# SDR-RPI_Shield_3_0.net
KiCad netlist of a schematic drawn in EAGLE
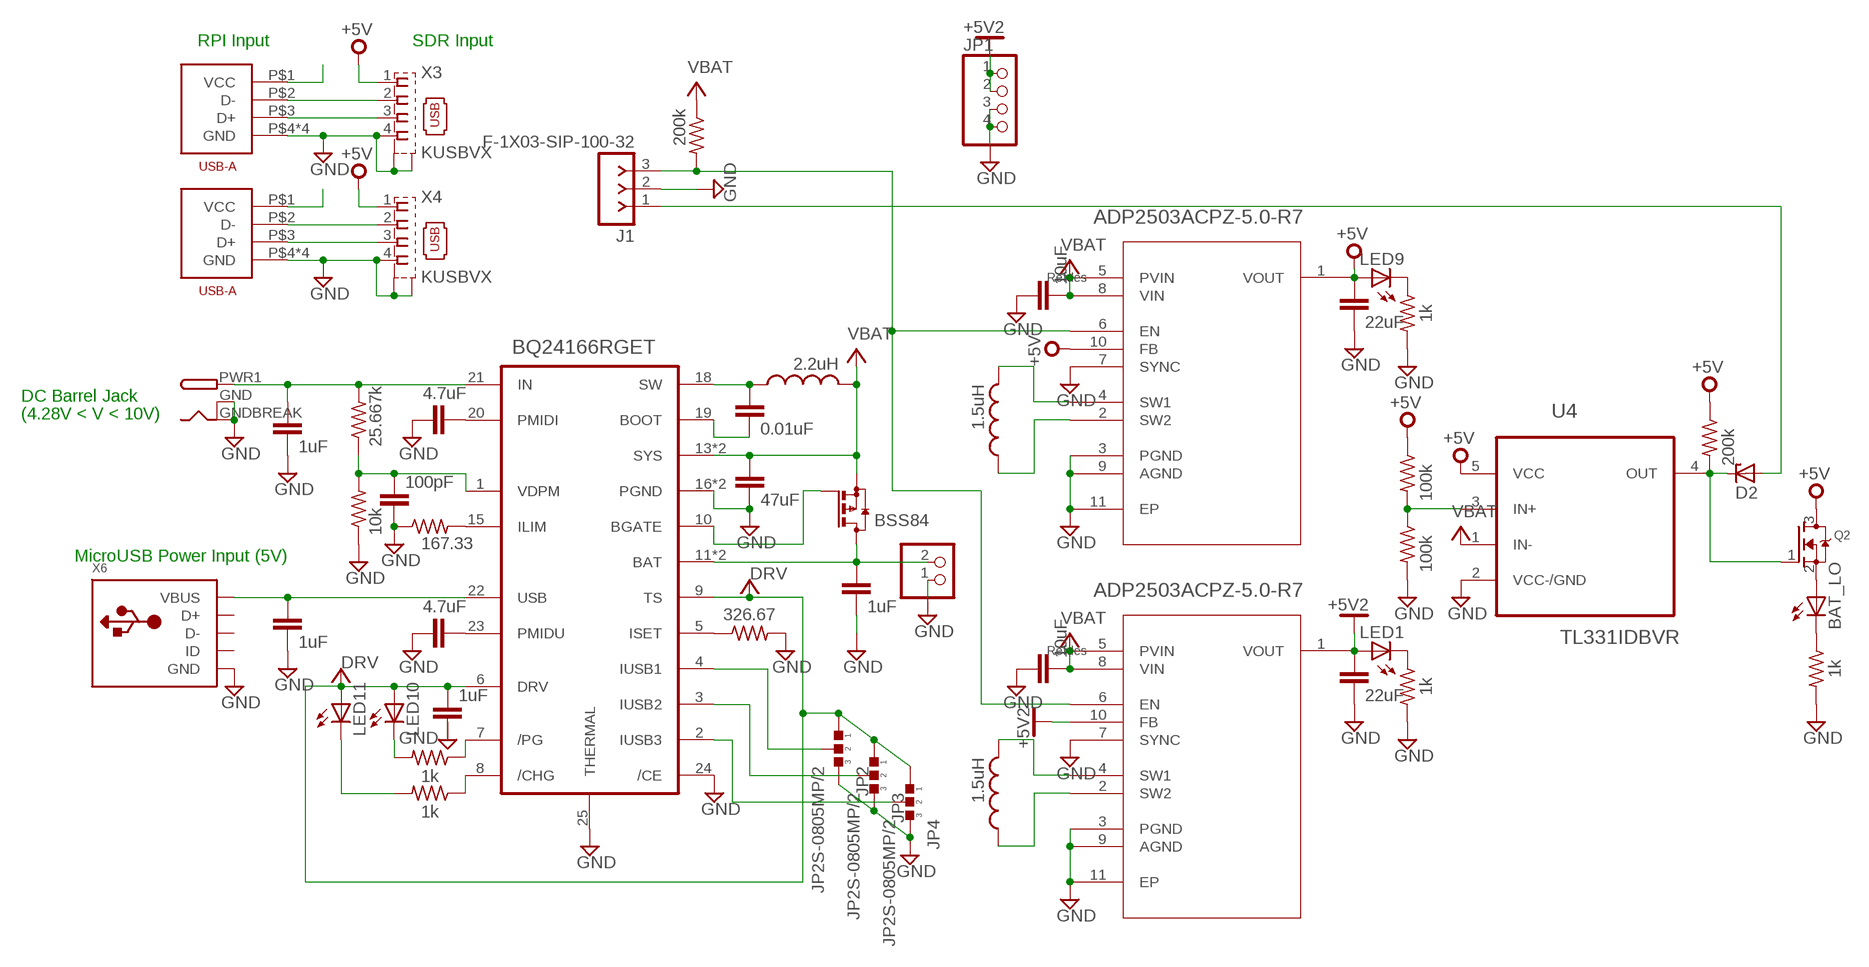
[diagram p0: schematic, sheet 1]

(export (version "E")
  (design (tool "Eeschema 10.0.6"))
  (components
    (comp (ref "BAT_LO")
      (value "LED_ESML0603")
      (footprint "eagle-import:LED_SML0603")
      (libsource (lib "eagle-import") (part "LED_ESML0603"))
    )
    (comp (ref "C1")
      (value "1uF")
      (footprint "eagle-import:C0805")
      (libsource (lib "eagle-import") (part "C-EUC0805"))
    )
    (comp (ref "C2")
      (value "4.7uF")
      (footprint "eagle-import:C0805")
      (libsource (lib "eagle-import") (part "C-EUC0805"))
    )
    (comp (ref "C3")
      (value "1uF")
      (footprint "eagle-import:C0805")
      (libsource (lib "eagle-import") (part "C-EUC0805"))
    )
    (comp (ref "C4")
      (value "4.7uF")
      (footprint "eagle-import:C0805")
      (libsource (lib "eagle-import") (part "C-EUC0805"))
    )
    (comp (ref "C5")
      (value "1uF")
      (footprint "eagle-import:C0805")
      (libsource (lib "eagle-import") (part "C-EUC0805"))
    )
    (comp (ref "C6")
      (value "0.01uF")
      (footprint "eagle-import:C0805")
      (libsource (lib "eagle-import") (part "C-EUC0805"))
    )
    (comp (ref "C7")
      (value "22uF")
      (footprint "eagle-import:C0805")
      (libsource (lib "eagle-import") (part "C-EUC0805"))
    )
    (comp (ref "C8")
      (value "1uF")
      (footprint "eagle-import:C0805")
      (libsource (lib "eagle-import") (part "C-EUC0805"))
    )
    (comp (ref "C9")
      (value "47uF")
      (footprint "eagle-import:C0805")
      (libsource (lib "eagle-import") (part "C-EUC0805"))
    )
    (comp (ref "C10")
      (value "10uF")
      (footprint "eagle-import:C0805")
      (libsource (lib "eagle-import") (part "C-EUC0805"))
    )
    (comp (ref "C11")
      (value "10uF")
      (footprint "eagle-import:C0805")
      (libsource (lib "eagle-import") (part "C-EUC0805"))
    )
    (comp (ref "C12")
      (value "22uF")
      (footprint "eagle-import:C0805")
      (libsource (lib "eagle-import") (part "C-EUC0805"))
    )
    (comp (ref "C17")
      (value "100pF")
      (footprint "eagle-import:C0805")
      (libsource (lib "eagle-import") (part "C-EUC0805"))
    )
    (comp (ref "CN1")
      (value "JST_2PIN-SMT")
      (footprint "eagle-import:JST-PH-2-SMT")
      (libsource (lib "eagle-import") (part "JST_2PIN-SMT"))
    )
    (comp (ref "CN3")
      (value "DCBARRELSMT")
      (footprint "eagle-import:DCJACK_2MM_SMT")
      (libsource (lib "eagle-import") (part "DCBARRELSMT"))
    )
    (comp (ref "D2")
      (value "ZENER-DIODESOD80C")
      (footprint "eagle-import:SOD80C")
      (libsource (lib "eagle-import") (part "ZENER-DIODESOD80C"))
    )
    (comp (ref "J1")
      (value "F-1X03-SIP-100-32")
      (footprint "eagle-import:SIP-100-03-32")
      (libsource (lib "eagle-import") (part "F-1X03-SIP-100-32"))
    )
    (comp (ref "JP1")
      (value "PINHD-1X4")
      (footprint "eagle-import:1X04")
      (libsource (lib "eagle-import") (part "PINHD-1X4"))
    )
    (comp (ref "JP2")
      (value "JP2S-0805MP/2")
      (footprint "eagle-import:R0805MP_2")
      (libsource (lib "eagle-import") (part "JP2S-0805MP/2"))
    )
    (comp (ref "JP3")
      (value "JP2S-0805MP/2")
      (footprint "eagle-import:R0805MP_2")
      (libsource (lib "eagle-import") (part "JP2S-0805MP/2"))
    )
    (comp (ref "JP4")
      (value "JP2S-0805MP/2")
      (footprint "eagle-import:R0805MP_2")
      (libsource (lib "eagle-import") (part "JP2S-0805MP/2"))
    )
    (comp (ref "L1")
      (value "2.2uH")
      (footprint "eagle-import:L1812")
      (libsource (lib "eagle-import") (part "L-USL1812"))
    )
    (comp (ref "L2")
      (value "1.5uH")
      (footprint "eagle-import:L1812")
      (libsource (lib "eagle-import") (part "L-USL1812"))
    )
    (comp (ref "L3")
      (value "1.5uH")
      (footprint "eagle-import:L1812")
      (libsource (lib "eagle-import") (part "L-USL1812"))
    )
    (comp (ref "LED1")
      (value "LED_ESML0603")
      (footprint "eagle-import:LED_SML0603")
      (libsource (lib "eagle-import") (part "LED_ESML0603"))
    )
    (comp (ref "LED9")
      (value "LED_ESML0603")
      (footprint "eagle-import:LED_SML0603")
      (libsource (lib "eagle-import") (part "LED_ESML0603"))
    )
    (comp (ref "LED10")
      (value "LED_ESML0603")
      (footprint "eagle-import:LED_SML0603")
      (libsource (lib "eagle-import") (part "LED_ESML0603"))
    )
    (comp (ref "LED11")
      (value "LED_ESML0603")
      (footprint "eagle-import:LED_SML0603")
      (libsource (lib "eagle-import") (part "LED_ESML0603"))
    )
    (comp (ref "Q1")
      (value "BSS84")
      (footprint "eagle-import:SOT23")
      (libsource (lib "eagle-import") (part "BSS84"))
    )
    (comp (ref "Q2")
      (value "MOSFET-NREFLOW")
      (footprint "eagle-import:SOT23")
      (libsource (lib "eagle-import") (part "MOSFET-NREFLOW"))
    )
    (comp (ref "R1")
      (value "25.667k")
      (footprint "eagle-import:M0805")
      (libsource (lib "eagle-import") (part "R-US_M0805"))
    )
    (comp (ref "R2")
      (value "10k")
      (footprint "eagle-import:M0805")
      (libsource (lib "eagle-import") (part "R-US_M0805"))
    )
    (comp (ref "R3")
      (value "167.33")
      (footprint "eagle-import:M0805")
      (libsource (lib "eagle-import") (part "R-US_M0805"))
    )
    (comp (ref "R4")
      (value "1k")
      (footprint "eagle-import:M0805")
      (libsource (lib "eagle-import") (part "R-US_M0805"))
    )
    (comp (ref "R5")
      (value "1k")
      (footprint "eagle-import:M0805")
      (libsource (lib "eagle-import") (part "R-US_M0805"))
    )
    (comp (ref "R6")
      (value "326.67")
      (footprint "eagle-import:M0805")
      (libsource (lib "eagle-import") (part "R-US_M0805"))
    )
    (comp (ref "R7")
      (value "1k")
      (footprint "eagle-import:M0805")
      (libsource (lib "eagle-import") (part "R-US_M0805"))
    )
    (comp (ref "R8")
      (value "1k")
      (footprint "eagle-import:M0805")
      (libsource (lib "eagle-import") (part "R-US_M0805"))
    )
    (comp (ref "R9")
      (value "100k")
      (footprint "eagle-import:M0805")
      (libsource (lib "eagle-import") (part "R-US_M0805"))
    )
    (comp (ref "R10")
      (value "100k")
      (footprint "eagle-import:M0805")
      (libsource (lib "eagle-import") (part "R-US_M0805"))
    )
    (comp (ref "R11")
      (value "200k")
      (footprint "eagle-import:M0805")
      (libsource (lib "eagle-import") (part "R-US_M0805"))
    )
    (comp (ref "R12")
      (value "1k")
      (footprint "eagle-import:M0805")
      (libsource (lib "eagle-import") (part "R-US_M0805"))
    )
    (comp (ref "R16")
      (value "200k")
      (footprint "eagle-import:M0805")
      (libsource (lib "eagle-import") (part "R-US_M0805"))
    )
    (comp (ref "U$1")
      (value "USB-A")
      (footprint "eagle-import:USB-A")
      (libsource (lib "eagle-import") (part "USB-A"))
    )
    (comp (ref "U$2")
      (value "USB-A")
      (footprint "eagle-import:USB-A")
      (libsource (lib "eagle-import") (part "USB-A"))
    )
    (comp (ref "U1")
      (value "BQ24166RGET")
      (footprint "eagle-import:QFN50P400X400X100-25N")
      (libsource (lib "eagle-import") (part "BQ24166RGET"))
    )
    (comp (ref "U2")
      (value "ADP2503ACPZ-5.0-R7")
      (footprint "eagle-import:DFN300X300X80-11N")
      (libsource (lib "eagle-import") (part "ADP2503ACPZ-5.0-R7"))
    )
    (comp (ref "U3")
      (value "ADP2503ACPZ-5.0-R7")
      (footprint "eagle-import:DFN300X300X80-11N")
      (libsource (lib "eagle-import") (part "ADP2503ACPZ-5.0-R7"))
    )
    (comp (ref "U4")
      (value "TL331IDBVR")
      (footprint "eagle-import:SOT95P280X145-5N")
      (libsource (lib "eagle-import") (part "TL331IDBVR"))
    )
    (comp (ref "X3")
      (value "KUSBVX")
      (footprint "eagle-import:KUSBVX")
      (libsource (lib "eagle-import") (part "KUSBVX"))
    )
    (comp (ref "X4")
      (value "KUSBVX")
      (footprint "eagle-import:KUSBVX")
      (libsource (lib "eagle-import") (part "KUSBVX"))
    )
    (comp (ref "X6")
      (value "USB_MICRO_20329_V2")
      (footprint "eagle-import:4UCONN_20329_V2")
      (libsource (lib "eagle-import") (part "USB_MICRO_20329_V2"))
    )
  )
  (nets
    (net (code "1") (name "+5V") (class "Default")
      (node (ref "C12") (pin "1") (pinfunction "1_1") (pintype "passive"))
      (node (ref "LED9") (pin "A") (pinfunction "A_A") (pintype "passive"))
      (node (ref "Q2") (pin "3") (pinfunction "D_3") (pintype "bidirectional"))
      (node (ref "R11") (pin "1") (pinfunction "1_1") (pintype "passive"))
      (node (ref "R9") (pin "1") (pinfunction "1_1") (pintype "passive"))
      (node (ref "U3") (pin "1") (pinfunction "VOUT_1") (pintype "output"))
      (node (ref "U3") (pin "10") (pinfunction "FB_10") (pintype "input"))
      (node (ref "U4") (pin "5") (pinfunction "VCC_5") (pintype "passive"))
      (node (ref "X3") (pin "1") (pinfunction "1_1") (pintype "passive"))
      (node (ref "X4") (pin "1") (pinfunction "1_1") (pintype "passive"))
    )
    (net (code "2") (name "+5V2") (class "Default")
      (node (ref "C7") (pin "1") (pinfunction "1_1") (pintype "passive"))
      (node (ref "JP1") (pin "1") (pinfunction "1_1") (pintype "passive"))
      (node (ref "JP1") (pin "2") (pinfunction "2_2") (pintype "passive"))
      (node (ref "LED1") (pin "A") (pinfunction "A_A") (pintype "passive"))
      (node (ref "U2") (pin "1") (pinfunction "VOUT_1") (pintype "output"))
      (node (ref "U2") (pin "10") (pinfunction "FB_10") (pintype "input"))
    )
    (net (code "3") (name "DRV") (class "Default")
      (node (ref "C5") (pin "1") (pinfunction "1_1") (pintype "passive"))
      (node (ref "JP2") (pin "1") (pinfunction "1_1") (pintype "passive"))
      (node (ref "JP3") (pin "1") (pinfunction "1_1") (pintype "passive"))
      (node (ref "JP4") (pin "1") (pinfunction "1_1") (pintype "passive"))
      (node (ref "LED10") (pin "A") (pinfunction "A_A") (pintype "passive"))
      (node (ref "LED11") (pin "A") (pinfunction "A_A") (pintype "passive"))
      (node (ref "U1") (pin "6") (pinfunction "DRV_6") (pintype "passive"))
      (node (ref "U1") (pin "9") (pinfunction "TS_9") (pintype "bidirectional"))
    )
    (net (code "4") (name "GND") (class "Default")
      (node (ref "C1") (pin "2") (pinfunction "2_2") (pintype "passive"))
      (node (ref "C10") (pin "1") (pinfunction "1_1") (pintype "passive"))
      (node (ref "C11") (pin "1") (pinfunction "1_1") (pintype "passive"))
      (node (ref "C12") (pin "2") (pinfunction "2_2") (pintype "passive"))
      (node (ref "C17") (pin "2") (pinfunction "2_2") (pintype "passive"))
      (node (ref "C2") (pin "2") (pinfunction "2_2") (pintype "passive"))
      (node (ref "C3") (pin "2") (pinfunction "2_2") (pintype "passive"))
      (node (ref "C4") (pin "2") (pinfunction "2_2") (pintype "passive"))
      (node (ref "C5") (pin "2") (pinfunction "2_2") (pintype "passive"))
      (node (ref "C7") (pin "2") (pinfunction "2_2") (pintype "passive"))
      (node (ref "C8") (pin "2") (pinfunction "2_2") (pintype "passive"))
      (node (ref "C9") (pin "2") (pinfunction "2_2") (pintype "passive"))
      (node (ref "CN1") (pin "1") (pinfunction "2_1") (pintype "passive"))
      (node (ref "CN3") (pin "GND") (pinfunction "GNDBREAK_GND") (pintype "power_in"))
      (node (ref "CN3") (pin "GNDBREAK") (pinfunction "GND_GNDBREAK") (pintype "power_in"))
      (node (ref "J1") (pin "2") (pinfunction "2_2") (pintype "passive"))
      (node (ref "JP1") (pin "3") (pinfunction "3_3") (pintype "passive"))
      (node (ref "JP1") (pin "4") (pinfunction "4_4") (pintype "passive"))
      (node (ref "JP2") (pin "3") (pinfunction "3_3") (pintype "passive"))
      (node (ref "JP3") (pin "3") (pinfunction "3_3") (pintype "passive"))
      (node (ref "JP4") (pin "3") (pinfunction "3_3") (pintype "passive"))
      (node (ref "R10") (pin "2") (pinfunction "2_2") (pintype "passive"))
      (node (ref "R12") (pin "2") (pinfunction "2_2") (pintype "passive"))
      (node (ref "R2") (pin "1") (pinfunction "1_1") (pintype "passive"))
      (node (ref "R3") (pin "1") (pinfunction "1_1") (pintype "passive"))
      (node (ref "R6") (pin "2") (pinfunction "2_2") (pintype "passive"))
      (node (ref "R7") (pin "2") (pinfunction "2_2") (pintype "passive"))
      (node (ref "R8") (pin "2") (pinfunction "2_2") (pintype "passive"))
      (node (ref "U$1") (pin "P$4") (pinfunction "GND_P$4") (pintype "power_in"))
      (node (ref "U$1") (pin "P$5") (pinfunction "GND_P$5") (pintype "power_in"))
      (node (ref "U$1") (pin "P$6") (pinfunction "GND_P$6") (pintype "power_in"))
      (node (ref "U$1") (pin "P$8") (pinfunction "GND_P$8") (pintype "power_in"))
      (node (ref "U$2") (pin "P$4") (pinfunction "GND_P$4") (pintype "power_in"))
      (node (ref "U$2") (pin "P$5") (pinfunction "GND_P$5") (pintype "power_in"))
      (node (ref "U$2") (pin "P$6") (pinfunction "GND_P$6") (pintype "power_in"))
      (node (ref "U$2") (pin "P$8") (pinfunction "GND_P$8") (pintype "power_in"))
      (node (ref "U1") (pin "16") (pinfunction "PGND_16") (pintype "output"))
      (node (ref "U1") (pin "17") (pinfunction "PGND_17") (pintype "output"))
      (node (ref "U1") (pin "24") (pinfunction "/CE_24") (pintype "bidirectional"))
      (node (ref "U1") (pin "25") (pinfunction "THERMAL_25") (pintype "bidirectional"))
      (node (ref "U2") (pin "11") (pinfunction "EP_11") (pintype "passive"))
      (node (ref "U2") (pin "3") (pinfunction "PGND_3") (pintype "passive"))
      (node (ref "U2") (pin "7") (pinfunction "SYNC_7") (pintype "input"))
      (node (ref "U2") (pin "9") (pinfunction "AGND_9") (pintype "passive"))
      (node (ref "U3") (pin "11") (pinfunction "EP_11") (pintype "passive"))
      (node (ref "U3") (pin "3") (pinfunction "PGND_3") (pintype "passive"))
      (node (ref "U3") (pin "7") (pinfunction "SYNC_7") (pintype "input"))
      (node (ref "U3") (pin "9") (pinfunction "AGND_9") (pintype "passive"))
      (node (ref "U4") (pin "2") (pinfunction "VCC-/GND_2") (pintype "passive"))
      (node (ref "X3") (pin "4") (pinfunction "4_4") (pintype "passive"))
      (node (ref "X3") (pin "M1") (pinfunction "S1_M1") (pintype "passive"))
      (node (ref "X3") (pin "M2") (pinfunction "S2_M2") (pintype "passive"))
      (node (ref "X4") (pin "4") (pinfunction "4_4") (pintype "passive"))
      (node (ref "X4") (pin "M1") (pinfunction "S1_M1") (pintype "passive"))
      (node (ref "X4") (pin "M2") (pinfunction "S2_M2") (pintype "passive"))
      (node (ref "X6") (pin "BASE@1") (pinfunction "GND_BASE@1") (pintype "power_in"))
      (node (ref "X6") (pin "BASE@2") (pinfunction "GND_BASE@2") (pintype "power_in"))
      (node (ref "X6") (pin "GND") (pinfunction "GND_GND") (pintype "power_in"))
      (node (ref "X6") (pin "SPRT@1") (pinfunction "GND_SPRT@1") (pintype "power_in"))
      (node (ref "X6") (pin "SPRT@2") (pinfunction "GND_SPRT@2") (pintype "power_in"))
      (node (ref "X6") (pin "SPRT@3") (pinfunction "GND_SPRT@3") (pintype "power_in"))
      (node (ref "X6") (pin "SPRT@4") (pinfunction "GND_SPRT@4") (pintype "power_in"))
    )
    (net (code "5") (name "Net-(BAT_LO-PadC)") (class "Default")
      (node (ref "BAT_LO") (pin "C") (pinfunction "C_C") (pintype "passive"))
      (node (ref "R12") (pin "1") (pinfunction "1_1") (pintype "passive"))
    )
    (net (code "6") (name "Net-(CN1-1)") (class "Default")
      (node (ref "C8") (pin "1") (pinfunction "1_1") (pintype "passive"))
      (node (ref "CN1") (pin "2") (pinfunction "1_2") (pintype "passive"))
      (node (ref "Q1") (pin "3") (pinfunction "D_3") (pintype "passive"))
      (node (ref "U1") (pin "11") (pinfunction "BAT_11") (pintype "input"))
      (node (ref "U1") (pin "12") (pinfunction "BAT_12") (pintype "input"))
    )
    (net (code "7") (name "Net-(CN3-PWR)") (class "Default")
      (node (ref "C1") (pin "1") (pinfunction "1_1") (pintype "passive"))
      (node (ref "CN3") (pin "PWR1") (pinfunction "PWR_PWR1") (pintype "power_in"))
      (node (ref "R1") (pin "2") (pinfunction "2_2") (pintype "passive"))
      (node (ref "U1") (pin "21") (pinfunction "IN_21") (pintype "power_in"))
    )
    (net (code "8") (name "Net-(D2-PadA)") (class "Default")
      (node (ref "D2") (pin "A") (pinfunction "A_A") (pintype "passive"))
      (node (ref "J1") (pin "1") (pinfunction "1_1") (pintype "passive"))
    )
    (net (code "9") (name "Net-(LED1-PadC)") (class "Default")
      (node (ref "LED1") (pin "C") (pinfunction "C_C") (pintype "passive"))
      (node (ref "R7") (pin "1") (pinfunction "1_1") (pintype "passive"))
    )
    (net (code "10") (name "Net-(LED9-PadC)") (class "Default")
      (node (ref "LED9") (pin "C") (pinfunction "C_C") (pintype "passive"))
      (node (ref "R8") (pin "1") (pinfunction "1_1") (pintype "passive"))
    )
    (net (code "11") (name "Net-(LED10-PadC)") (class "Default")
      (node (ref "LED10") (pin "C") (pinfunction "C_C") (pintype "passive"))
      (node (ref "R4") (pin "2") (pinfunction "2_2") (pintype "passive"))
    )
    (net (code "12") (name "Net-(LED11-PadC)") (class "Default")
      (node (ref "LED11") (pin "C") (pinfunction "C_C") (pintype "passive"))
      (node (ref "R5") (pin "2") (pinfunction "2_2") (pintype "passive"))
    )
    (net (code "13") (name "Net-(Q1-G)") (class "Default")
      (node (ref "Q1") (pin "1") (pinfunction "G_1") (pintype "passive"))
      (node (ref "U1") (pin "10") (pinfunction "BGATE_10") (pintype "bidirectional"))
    )
    (net (code "14") (name "Net-(Q2-G)") (class "Default")
      (node (ref "D2") (pin "C") (pinfunction "C_C") (pintype "passive"))
      (node (ref "Q2") (pin "1") (pinfunction "G_1") (pintype "bidirectional"))
      (node (ref "R11") (pin "2") (pinfunction "2_2") (pintype "passive"))
      (node (ref "U4") (pin "4") (pinfunction "OUT_4") (pintype "passive"))
    )
    (net (code "15") (name "Net-(Q2-S)") (class "Default")
      (node (ref "BAT_LO") (pin "A") (pinfunction "A_A") (pintype "passive"))
      (node (ref "Q2") (pin "2") (pinfunction "S_2") (pintype "bidirectional"))
    )
    (net (code "16") (name "Net-(U$1-D+)") (class "Default")
      (node (ref "U$1") (pin "P$3") (pinfunction "D+_P$3") (pintype "bidirectional"))
      (node (ref "X3") (pin "3") (pinfunction "3_3") (pintype "passive"))
    )
    (net (code "17") (name "Net-(U$1-D-)") (class "Default")
      (node (ref "U$1") (pin "P$2") (pinfunction "D-_P$2") (pintype "bidirectional"))
      (node (ref "X3") (pin "2") (pinfunction "2_2") (pintype "passive"))
    )
    (net (code "18") (name "Net-(U$2-D+)") (class "Default")
      (node (ref "U$2") (pin "P$3") (pinfunction "D+_P$3") (pintype "bidirectional"))
      (node (ref "X4") (pin "3") (pinfunction "3_3") (pintype "passive"))
    )
    (net (code "19") (name "Net-(U$2-D-)") (class "Default")
      (node (ref "U$2") (pin "P$2") (pinfunction "D-_P$2") (pintype "bidirectional"))
      (node (ref "X4") (pin "2") (pinfunction "2_2") (pintype "passive"))
    )
    (net (code "20") (name "Net-(U1-BOOT)") (class "Default")
      (node (ref "C6") (pin "2") (pinfunction "2_2") (pintype "passive"))
      (node (ref "U1") (pin "19") (pinfunction "BOOT_19") (pintype "bidirectional"))
    )
    (net (code "21") (name "Net-(U1-ILIM)") (class "Default")
      (node (ref "R3") (pin "2") (pinfunction "2_2") (pintype "passive"))
      (node (ref "U1") (pin "15") (pinfunction "ILIM_15") (pintype "bidirectional"))
    )
    (net (code "22") (name "Net-(U1-ISET)") (class "Default")
      (node (ref "R6") (pin "1") (pinfunction "1_1") (pintype "passive"))
      (node (ref "U1") (pin "5") (pinfunction "ISET_5") (pintype "bidirectional"))
    )
    (net (code "23") (name "Net-(U1-IUSB1)") (class "Default")
      (node (ref "JP2") (pin "2") (pinfunction "2_2") (pintype "passive"))
      (node (ref "U1") (pin "4") (pinfunction "IUSB1_4") (pintype "input"))
    )
    (net (code "24") (name "Net-(U1-IUSB2)") (class "Default")
      (node (ref "JP3") (pin "2") (pinfunction "2_2") (pintype "passive"))
      (node (ref "U1") (pin "3") (pinfunction "IUSB2_3") (pintype "input"))
    )
    (net (code "25") (name "Net-(U1-IUSB3)") (class "Default")
      (node (ref "JP4") (pin "2") (pinfunction "2_2") (pintype "passive"))
      (node (ref "U1") (pin "2") (pinfunction "IUSB3_2") (pintype "input"))
    )
    (net (code "26") (name "Net-(U1-PMIDI)") (class "Default")
      (node (ref "C2") (pin "1") (pinfunction "1_1") (pintype "passive"))
      (node (ref "U1") (pin "20") (pinfunction "PMIDI_20") (pintype "passive"))
    )
    (net (code "27") (name "Net-(U1-PMIDU)") (class "Default")
      (node (ref "C4") (pin "1") (pinfunction "1_1") (pintype "passive"))
      (node (ref "U1") (pin "23") (pinfunction "PMIDU_23") (pintype "input"))
    )
    (net (code "28") (name "Net-(U1-SW)") (class "Default")
      (node (ref "C6") (pin "1") (pinfunction "1_1") (pintype "passive"))
      (node (ref "L1") (pin "1") (pinfunction "1_1") (pintype "passive"))
      (node (ref "U1") (pin "18") (pinfunction "SW_18") (pintype "bidirectional"))
    )
    (net (code "29") (name "Net-(U1-USB)") (class "Default")
      (node (ref "C3") (pin "1") (pinfunction "1_1") (pintype "passive"))
      (node (ref "U1") (pin "22") (pinfunction "USB_22") (pintype "input"))
      (node (ref "X6") (pin "VBUS") (pinfunction "VBUS_VBUS") (pintype "power_in"))
    )
    (net (code "30") (name "Net-(U1-VDPM)") (class "Default")
      (node (ref "C17") (pin "1") (pinfunction "1_1") (pintype "passive"))
      (node (ref "R1") (pin "1") (pinfunction "1_1") (pintype "passive"))
      (node (ref "R2") (pin "2") (pinfunction "2_2") (pintype "passive"))
      (node (ref "U1") (pin "1") (pinfunction "VDPM_1") (pintype "input"))
    )
    (net (code "31") (name "Net-(U1-{slash}CHG)") (class "Default")
      (node (ref "R5") (pin "1") (pinfunction "1_1") (pintype "passive"))
      (node (ref "U1") (pin "8") (pinfunction "/CHG_8") (pintype "output"))
    )
    (net (code "32") (name "Net-(U1-{slash}PG)") (class "Default")
      (node (ref "R4") (pin "1") (pinfunction "1_1") (pintype "passive"))
      (node (ref "U1") (pin "7") (pinfunction "/PG_7") (pintype "output"))
    )
    (net (code "33") (name "Net-(U2-EN)") (class "Default")
      (node (ref "J1") (pin "3") (pinfunction "3_3") (pintype "passive"))
      (node (ref "R16") (pin "2") (pinfunction "2_2") (pintype "passive"))
      (node (ref "U2") (pin "6") (pinfunction "EN_6") (pintype "input"))
      (node (ref "U3") (pin "6") (pinfunction "EN_6") (pintype "input"))
    )
    (net (code "34") (name "Net-(U2-SW1)") (class "Default")
      (node (ref "L3") (pin "2") (pinfunction "2_2") (pintype "passive"))
      (node (ref "U2") (pin "4") (pinfunction "SW1_4") (pintype "passive"))
    )
    (net (code "35") (name "Net-(U2-SW2)") (class "Default")
      (node (ref "L3") (pin "1") (pinfunction "1_1") (pintype "passive"))
      (node (ref "U2") (pin "2") (pinfunction "SW2_2") (pintype "passive"))
    )
    (net (code "36") (name "Net-(U3-SW1)") (class "Default")
      (node (ref "L2") (pin "2") (pinfunction "2_2") (pintype "passive"))
      (node (ref "U3") (pin "4") (pinfunction "SW1_4") (pintype "passive"))
    )
    (net (code "37") (name "Net-(U3-SW2)") (class "Default")
      (node (ref "L2") (pin "1") (pinfunction "1_1") (pintype "passive"))
      (node (ref "U3") (pin "2") (pinfunction "SW2_2") (pintype "passive"))
    )
    (net (code "38") (name "Net-(U4-IN+)") (class "Default")
      (node (ref "R10") (pin "1") (pinfunction "1_1") (pintype "passive"))
      (node (ref "R9") (pin "2") (pinfunction "2_2") (pintype "passive"))
      (node (ref "U4") (pin "3") (pinfunction "IN+_3") (pintype "passive"))
    )
    (net (code "39") (name "VBAT") (class "Default")
      (node (ref "C10") (pin "2") (pinfunction "2_2") (pintype "passive"))
      (node (ref "C11") (pin "2") (pinfunction "2_2") (pintype "passive"))
      (node (ref "C9") (pin "1") (pinfunction "1_1") (pintype "passive"))
      (node (ref "L1") (pin "2") (pinfunction "2_2") (pintype "passive"))
      (node (ref "Q1") (pin "2") (pinfunction "S_2") (pintype "passive"))
      (node (ref "R16") (pin "1") (pinfunction "1_1") (pintype "passive"))
      (node (ref "U1") (pin "13") (pinfunction "SYS_13") (pintype "output"))
      (node (ref "U1") (pin "14") (pinfunction "SYS_14") (pintype "output"))
      (node (ref "U2") (pin "5") (pinfunction "PVIN_5") (pintype "power_in"))
      (node (ref "U2") (pin "8") (pinfunction "VIN_8") (pintype "power_in"))
      (node (ref "U3") (pin "5") (pinfunction "PVIN_5") (pintype "power_in"))
      (node (ref "U3") (pin "8") (pinfunction "VIN_8") (pintype "power_in"))
      (node (ref "U4") (pin "1") (pinfunction "IN-_1") (pintype "passive"))
    )
    (net (code "40") (name "unconnected-(U$1-VCC-PadP$1)") (class "Default")
      (node (ref "U$1") (pin "P$1") (pinfunction "VCC_P$1") (pintype "power_in"))
    )
    (net (code "41") (name "unconnected-(U$2-VCC-PadP$1)") (class "Default")
      (node (ref "U$2") (pin "P$1") (pinfunction "VCC_P$1") (pintype "power_in"))
    )
    (net (code "42") (name "unconnected-(X6-PadD+)") (class "Default")
      (node (ref "X6") (pin "D+") (pinfunction "D+_D+") (pintype "bidirectional"))
    )
    (net (code "43") (name "unconnected-(X6-PadD-)") (class "Default")
      (node (ref "X6") (pin "D-") (pinfunction "D-_D-") (pintype "bidirectional"))
    )
    (net (code "44") (name "unconnected-(X6-PadID)") (class "Default")
      (node (ref "X6") (pin "ID") (pinfunction "ID_ID") (pintype "bidirectional"))
    )
  )
)
